# ProPrj_2401336012_2401336029__2025-09-21.net
KiCad netlist of a schematic drawn in EasyEDA Pro
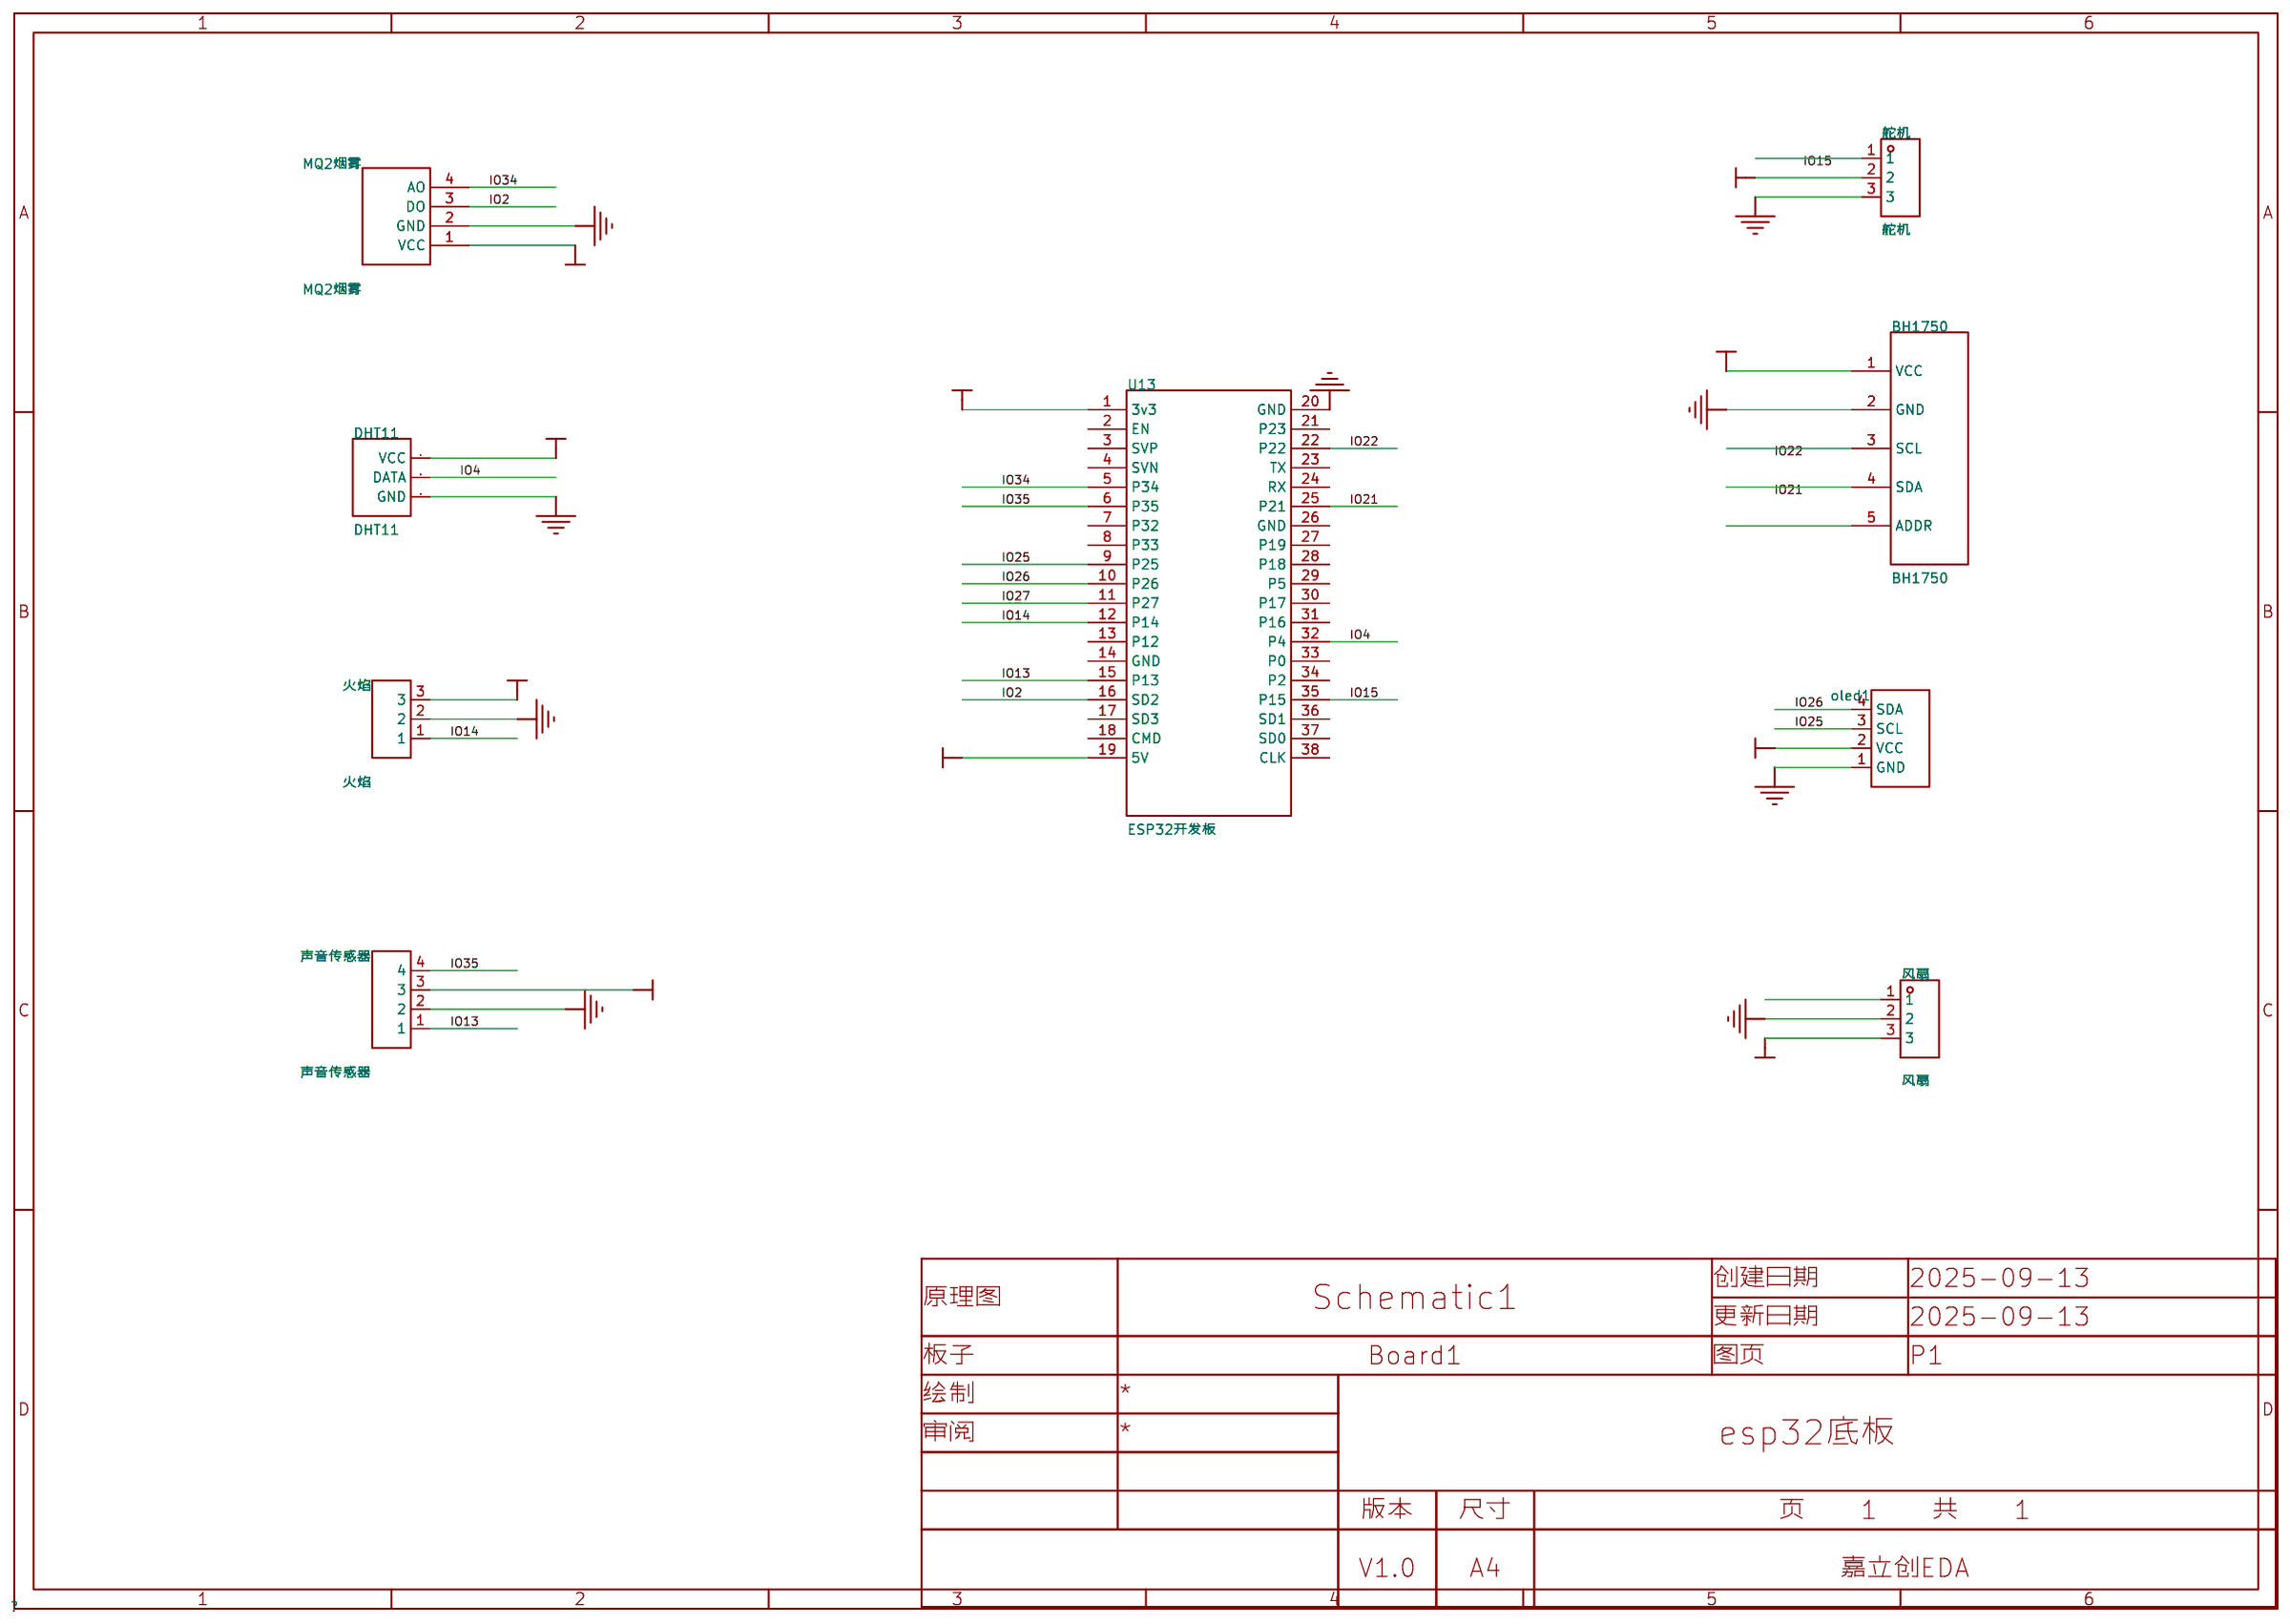
[diagram p0: schematic sheet]

(export (version "E")
  (design (tool "Eeschema 10.0.6"))
  (components
    (comp (ref "BH1750")
      (value "BH1750")
      (footprint "easyedapro:BH1750_(GY-302)")
      (libsource (lib "easyedapro") (part "BH1750"))
    )
    (comp (ref "DHT11")
      (value "DHT11")
      (footprint "easyedapro:DHT11_X")
      (libsource (lib "easyedapro") (part "DHT11"))
    )
    (comp (ref "MQ2烟雾")
      (value "MQ2烟雾")
      (footprint "easyedapro:mq2")
      (libsource (lib "easyedapro") (part "MQ2"))
    )
    (comp (ref "oled1")
      (value "OLED0.96")
      (footprint "easyedapro:OLED-0.96")
      (libsource (lib "easyedapro") (part "OLED0.96"))
    )
    (comp (ref "U13")
      (value "ESP32开发板")
      (footprint "easyedapro:ESP32___")
      (libsource (lib "easyedapro") (part "ESP32开发板"))
    )
    (comp (ref "声音传感器")
      (value "声音传感器")
      (footprint "easyedapro:HDR-TH_A254UP-ZD04P")
      (description "插针结构:1x4P;间距:2.54mm;行距:-;圆针/方针:方针;排数:单排;总PIN位数:4P;额定电流:3A;配合针长度:6mm;塑高:2.5mm;工作温度:-40℃~+105℃;")
      (fields (field (name "Manufacturer") "BXCONN(宝讯)"))
      (libsource (lib "easyedapro") (part "A254UP-ZD04P"))
    )
    (comp (ref "火焰")
      (value "火焰")
      (footprint "easyedapro:HDR-TH_3P-P2.54-V-M")
      (fields (field (name "Manufacturer") "XUNPU(讯普)"))
      (libsource (lib "easyedapro") (part "PH2.54-01-03PZD"))
    )
    (comp (ref "舵机")
      (value "PZ254V-11-03P")
      (footprint "easyedapro:HDR-TH_3P-P2.54-V-M")
      (fields (field (name "Manufacturer Part") "舵机") (field (name "Manufacturer") "XFCN(兴飞)"))
      (libsource (lib "easyedapro") (part "PZ254V-11-03P_C2937625"))
    )
    (comp (ref "风扇")
      (value "PZ254V-11-03P")
      (footprint "easyedapro:HDR-TH_3P-P2.54-V-M")
      (fields (field (name "Manufacturer Part") "风扇") (field (name "Manufacturer") "XFCN(兴飞)"))
      (libsource (lib "easyedapro") (part "PZ254V-11-03P_C2937625"))
    )
  )
  (nets
    (net (code "1") (name "+5V") (class "Default")
      (node (ref "MQ2烟雾") (pin "1") (pinfunction "VCC_1") (pintype "unspecified"))
      (node (ref "U13") (pin "19") (pinfunction "5V_19") (pintype "unspecified"))
      (node (ref "声音传感器") (pin "3") (pinfunction "3_3") (pintype "unspecified"))
      (node (ref "舵机") (pin "2") (pinfunction "2_2") (pintype "unspecified"))
      (node (ref "风扇") (pin "3") (pinfunction "3_3") (pintype "unspecified"))
    )
    (net (code "2") (name "/IO2") (class "Default")
      (node (ref "MQ2烟雾") (pin "3") (pinfunction "DO_3") (pintype "unspecified"))
      (node (ref "U13") (pin "16") (pinfunction "SD2_16") (pintype "unspecified"))
    )
    (net (code "3") (name "/IO4") (class "Default")
      (node (ref "DHT11") (pin "2") (pinfunction "DATA_2") (pintype "unspecified"))
      (node (ref "U13") (pin "32") (pinfunction "P4_32") (pintype "unspecified"))
    )
    (net (code "4") (name "/IO13") (class "Default")
      (node (ref "U13") (pin "15") (pinfunction "P13_15") (pintype "unspecified"))
      (node (ref "声音传感器") (pin "1") (pinfunction "1_1") (pintype "unspecified"))
    )
    (net (code "5") (name "/IO14") (class "Default")
      (node (ref "U13") (pin "12") (pinfunction "P14_12") (pintype "unspecified"))
      (node (ref "火焰") (pin "1") (pinfunction "1_1") (pintype "unspecified"))
    )
    (net (code "6") (name "/IO15") (class "Default")
      (node (ref "U13") (pin "35") (pinfunction "P15_35") (pintype "unspecified"))
      (node (ref "舵机") (pin "1") (pinfunction "1_1") (pintype "unspecified"))
    )
    (net (code "7") (name "/IO21") (class "Default")
      (node (ref "BH1750") (pin "4") (pinfunction "SDA_4") (pintype "unspecified"))
      (node (ref "U13") (pin "25") (pinfunction "P21_25") (pintype "unspecified"))
    )
    (net (code "8") (name "/IO22") (class "Default")
      (node (ref "BH1750") (pin "3") (pinfunction "SCL_3") (pintype "unspecified"))
      (node (ref "U13") (pin "22") (pinfunction "P22_22") (pintype "unspecified"))
    )
    (net (code "9") (name "/IO25") (class "Default")
      (node (ref "U13") (pin "9") (pinfunction "P25_9") (pintype "unspecified"))
      (node (ref "oled1") (pin "3") (pinfunction "SCL_3") (pintype "unspecified"))
    )
    (net (code "10") (name "/IO26") (class "Default")
      (node (ref "U13") (pin "10") (pinfunction "P26_10") (pintype "unspecified"))
      (node (ref "oled1") (pin "4") (pinfunction "SDA_4") (pintype "unspecified"))
    )
    (net (code "11") (name "/IO27") (class "Default")
      (node (ref "U13") (pin "11") (pinfunction "P27_11") (pintype "unspecified"))
    )
    (net (code "12") (name "/IO34") (class "Default")
      (node (ref "MQ2烟雾") (pin "4") (pinfunction "AO_4") (pintype "unspecified"))
      (node (ref "U13") (pin "5") (pinfunction "P34_5") (pintype "unspecified"))
    )
    (net (code "13") (name "/IO35") (class "Default")
      (node (ref "U13") (pin "6") (pinfunction "P35_6") (pintype "unspecified"))
      (node (ref "声音传感器") (pin "4") (pinfunction "4_4") (pintype "unspecified"))
    )
    (net (code "14") (name "GND") (class "Default")
      (node (ref "BH1750") (pin "2") (pinfunction "GND_2") (pintype "unspecified"))
      (node (ref "DHT11") (pin "3") (pinfunction "GND_3") (pintype "unspecified"))
      (node (ref "MQ2烟雾") (pin "2") (pinfunction "GND_2") (pintype "unspecified"))
      (node (ref "U13") (pin "20") (pinfunction "GND_20") (pintype "unspecified"))
      (node (ref "oled1") (pin "1") (pinfunction "GND_1") (pintype "unspecified"))
      (node (ref "声音传感器") (pin "2") (pinfunction "2_2") (pintype "unspecified"))
      (node (ref "火焰") (pin "2") (pinfunction "2_2") (pintype "unspecified"))
      (node (ref "舵机") (pin "3") (pinfunction "3_3") (pintype "unspecified"))
      (node (ref "风扇") (pin "2") (pinfunction "2_2") (pintype "unspecified"))
    )
    (net (code "15") (name "VCC") (class "Default")
      (node (ref "BH1750") (pin "1") (pinfunction "VCC_1") (pintype "unspecified"))
      (node (ref "DHT11") (pin "1") (pinfunction "VCC_1") (pintype "unspecified"))
      (node (ref "U13") (pin "1") (pinfunction "3v3_1") (pintype "unspecified"))
      (node (ref "oled1") (pin "2") (pinfunction "VCC_2") (pintype "unspecified"))
      (node (ref "火焰") (pin "3") (pinfunction "3_3") (pintype "unspecified"))
    )
    (net (code "16") (name "unconnected-(BH1750-ADDR-Pad5)") (class "Default")
      (node (ref "BH1750") (pin "5") (pinfunction "ADDR_5") (pintype "unspecified"))
    )
    (net (code "17") (name "unconnected-(U13-CLK-Pad38)") (class "Default")
      (node (ref "U13") (pin "38") (pinfunction "CLK_38") (pintype "unspecified"))
    )
    (net (code "18") (name "unconnected-(U13-CMD-Pad18)") (class "Default")
      (node (ref "U13") (pin "18") (pinfunction "CMD_18") (pintype "unspecified"))
    )
    (net (code "19") (name "unconnected-(U13-EN-Pad2)") (class "Default")
      (node (ref "U13") (pin "2") (pinfunction "EN_2") (pintype "unspecified"))
    )
    (net (code "20") (name "unconnected-(U13-GND-Pad14)") (class "Default")
      (node (ref "U13") (pin "14") (pinfunction "GND_14") (pintype "unspecified"))
    )
    (net (code "21") (name "unconnected-(U13-GND-Pad26)") (class "Default")
      (node (ref "U13") (pin "26") (pinfunction "GND_26") (pintype "unspecified"))
    )
    (net (code "22") (name "unconnected-(U13-P0-Pad33)") (class "Default")
      (node (ref "U13") (pin "33") (pinfunction "P0_33") (pintype "unspecified"))
    )
    (net (code "23") (name "unconnected-(U13-P2-Pad34)") (class "Default")
      (node (ref "U13") (pin "34") (pinfunction "P2_34") (pintype "unspecified"))
    )
    (net (code "24") (name "unconnected-(U13-P5-Pad29)") (class "Default")
      (node (ref "U13") (pin "29") (pinfunction "P5_29") (pintype "unspecified"))
    )
    (net (code "25") (name "unconnected-(U13-P12-Pad13)") (class "Default")
      (node (ref "U13") (pin "13") (pinfunction "P12_13") (pintype "unspecified"))
    )
    (net (code "26") (name "unconnected-(U13-P16-Pad31)") (class "Default")
      (node (ref "U13") (pin "31") (pinfunction "P16_31") (pintype "unspecified"))
    )
    (net (code "27") (name "unconnected-(U13-P17-Pad30)") (class "Default")
      (node (ref "U13") (pin "30") (pinfunction "P17_30") (pintype "unspecified"))
    )
    (net (code "28") (name "unconnected-(U13-P18-Pad28)") (class "Default")
      (node (ref "U13") (pin "28") (pinfunction "P18_28") (pintype "unspecified"))
    )
    (net (code "29") (name "unconnected-(U13-P19-Pad27)") (class "Default")
      (node (ref "U13") (pin "27") (pinfunction "P19_27") (pintype "unspecified"))
    )
    (net (code "30") (name "unconnected-(U13-P23-Pad21)") (class "Default")
      (node (ref "U13") (pin "21") (pinfunction "P23_21") (pintype "unspecified"))
    )
    (net (code "31") (name "unconnected-(U13-P32-Pad7)") (class "Default")
      (node (ref "U13") (pin "7") (pinfunction "P32_7") (pintype "unspecified"))
    )
    (net (code "32") (name "unconnected-(U13-P33-Pad8)") (class "Default")
      (node (ref "U13") (pin "8") (pinfunction "P33_8") (pintype "unspecified"))
    )
    (net (code "33") (name "unconnected-(U13-RX-Pad24)") (class "Default")
      (node (ref "U13") (pin "24") (pinfunction "RX_24") (pintype "unspecified"))
    )
    (net (code "34") (name "unconnected-(U13-SD0-Pad37)") (class "Default")
      (node (ref "U13") (pin "37") (pinfunction "SD0_37") (pintype "unspecified"))
    )
    (net (code "35") (name "unconnected-(U13-SD1-Pad36)") (class "Default")
      (node (ref "U13") (pin "36") (pinfunction "SD1_36") (pintype "unspecified"))
    )
    (net (code "36") (name "unconnected-(U13-SD3-Pad17)") (class "Default")
      (node (ref "U13") (pin "17") (pinfunction "SD3_17") (pintype "unspecified"))
    )
    (net (code "37") (name "unconnected-(U13-SVN-Pad4)") (class "Default")
      (node (ref "U13") (pin "4") (pinfunction "SVN_4") (pintype "unspecified"))
    )
    (net (code "38") (name "unconnected-(U13-SVP-Pad3)") (class "Default")
      (node (ref "U13") (pin "3") (pinfunction "SVP_3") (pintype "unspecified"))
    )
    (net (code "39") (name "unconnected-(U13-TX-Pad23)") (class "Default")
      (node (ref "U13") (pin "23") (pinfunction "TX_23") (pintype "unspecified"))
    )
    (net (code "40") (name "unconnected-(风扇-Pad1)") (class "Default")
      (node (ref "风扇") (pin "1") (pinfunction "1_1") (pintype "unspecified"))
    )
  )
)
